# RP2350-MLX90393_4.net
KiCad netlist of a schematic drawn in EasyEDA Pro
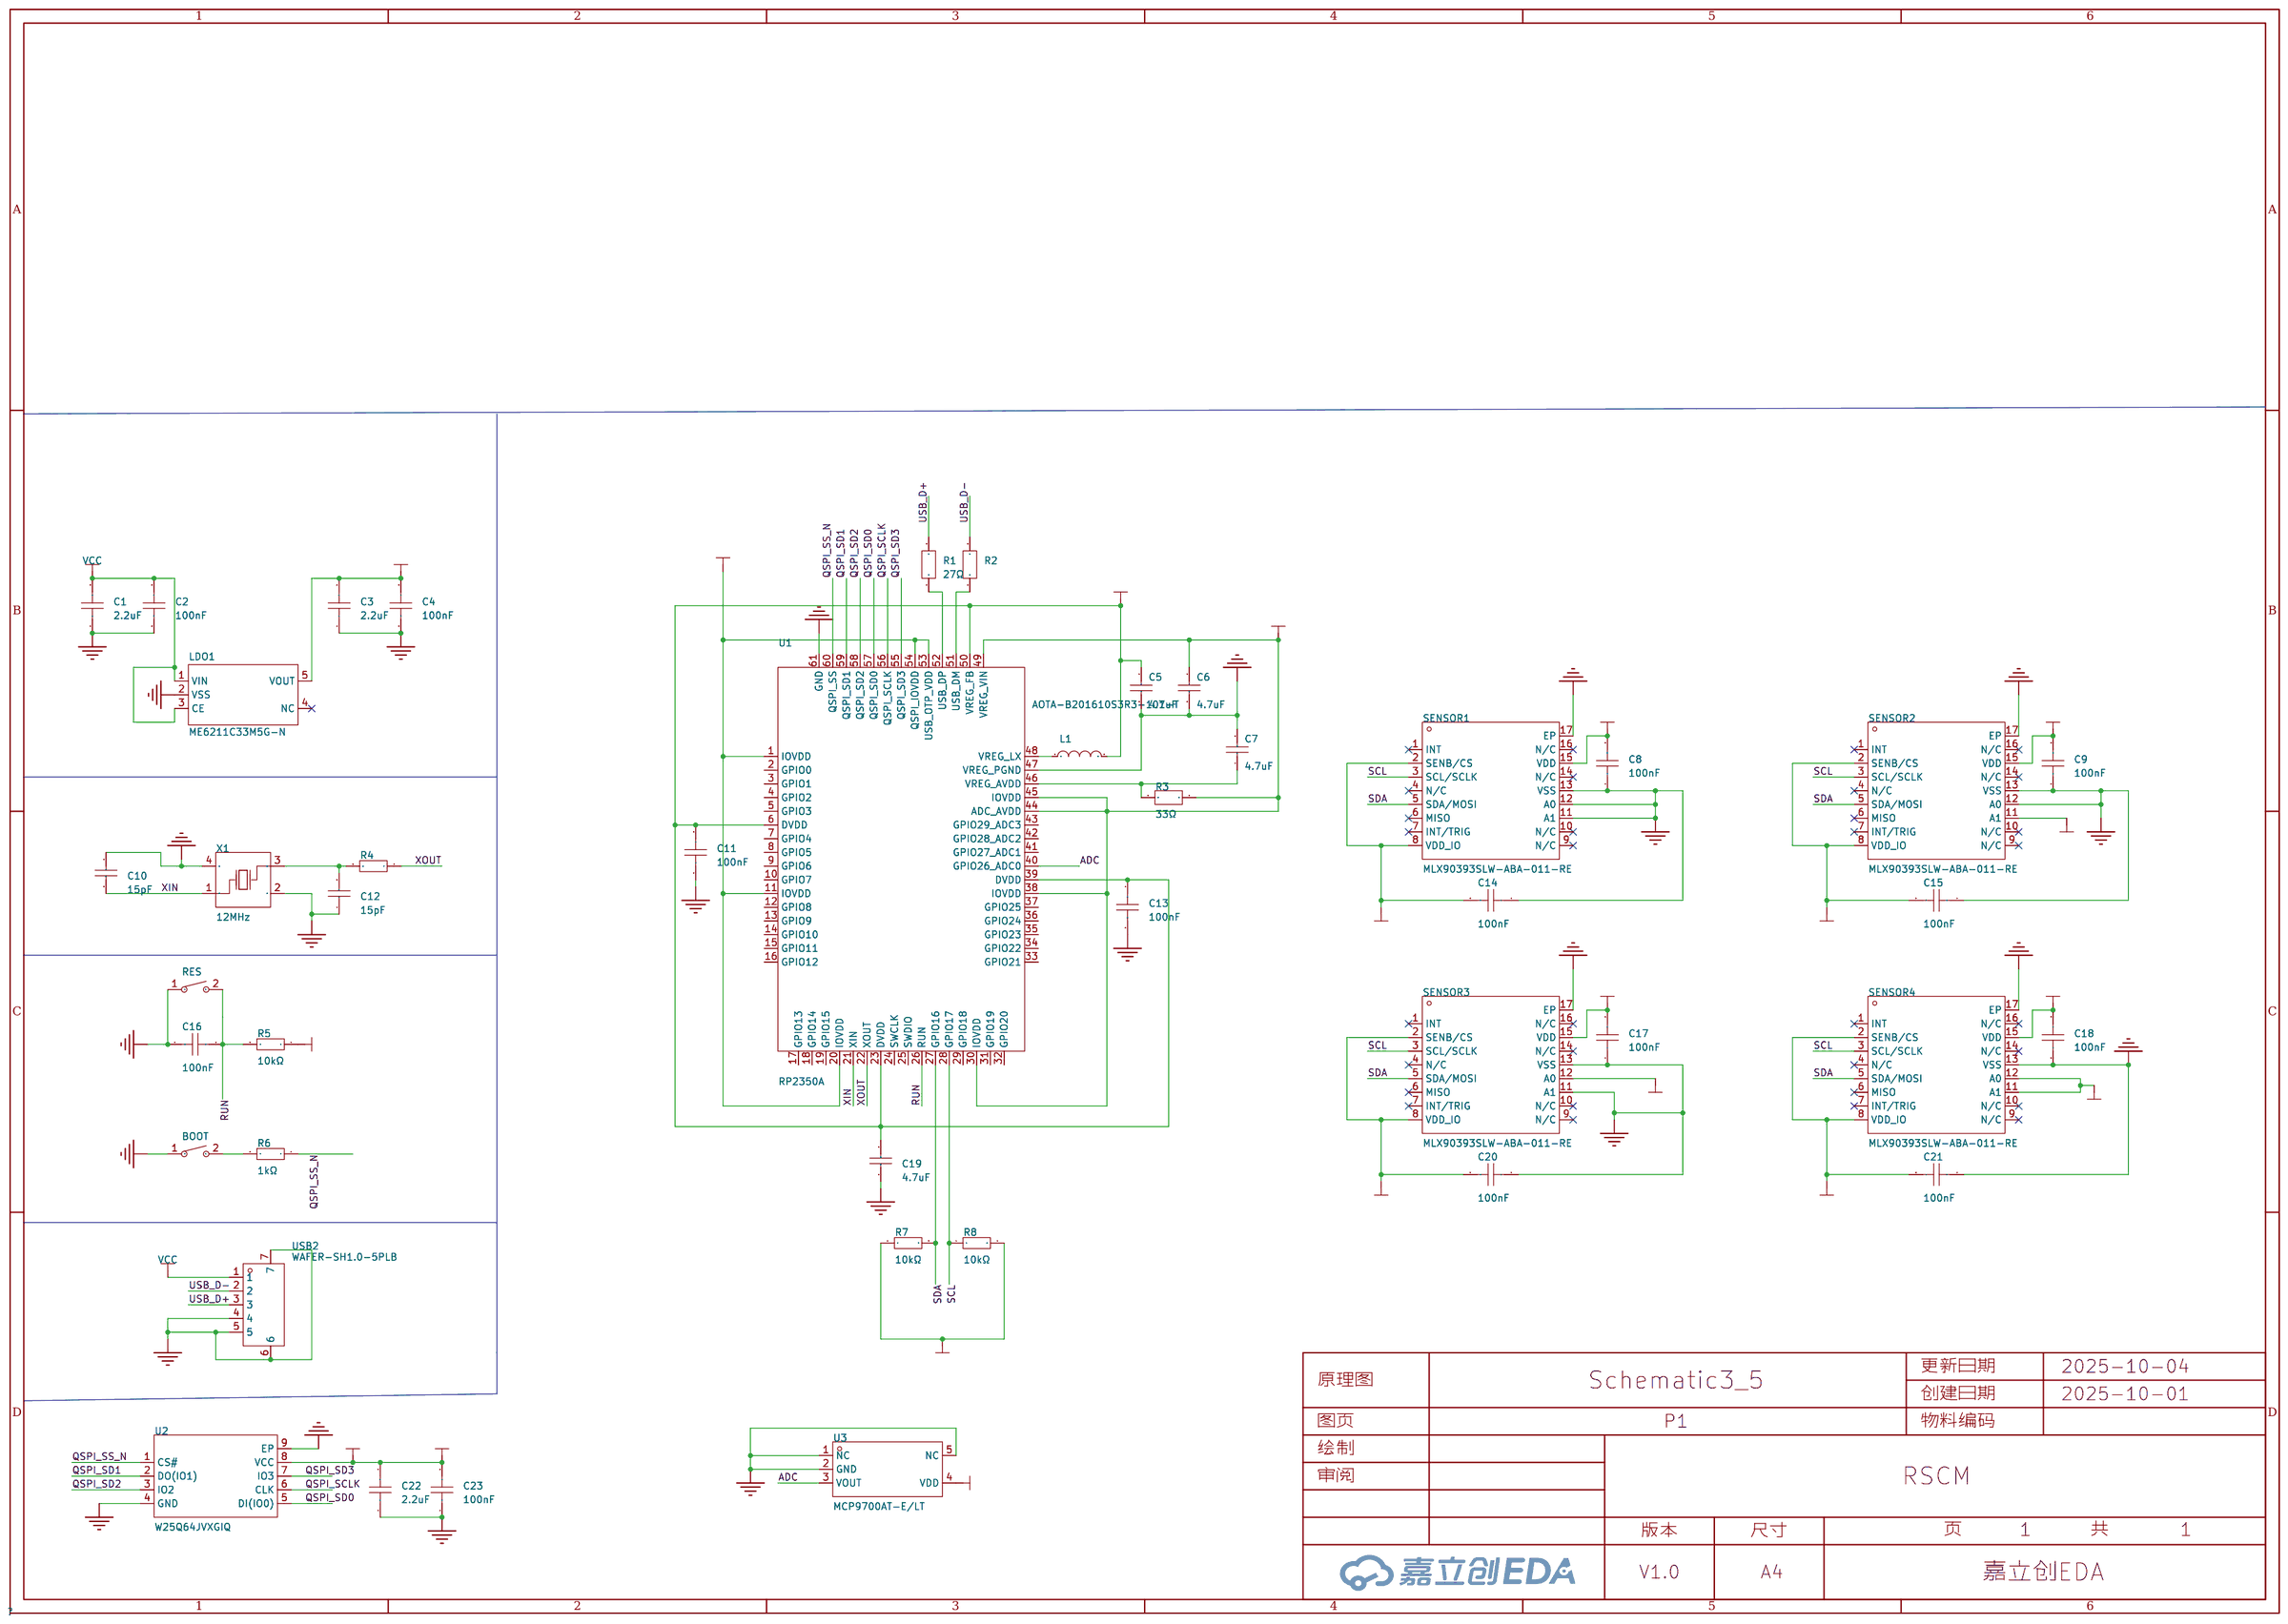
[diagram p0: schematic sheet]

(export (version "E")
  (design (tool "Eeschema 10.0.6"))
  (components
    (comp (ref "BOOT")
      (value "TS-1071AD-A1B3-D4")
      (footprint "easyedapro:SW-SMD_L4.0-W3.0-LS4.8")
      (description "电路结构:单刀单掷;安装方式:-;按钮形状:圆形按钮;带灯:-;作用力:250gf@±30gf;开关长度:4mm;开关宽度:3mm;开关高度:2mm;")
      (fields (field (name "Manufacturer") "Yuandi(元迪)"))
      (libsource (lib "easyedapro") (part "TS-1071AD-A1B3-D4"))
    )
    (comp (ref "C1")
      (value "2.2uF")
      (footprint "easyedapro:C0603")
      (description "容值:2.2uF;精度:±10%;额定电压:50V;材质(温度系数):X5R;")
      (fields
        (field (name "Manufacturer Part") "CL10A225KB8NNNC")
        (field (name "Manufacturer") "SAMSUNG(三星)")
      )
      (libsource (lib "easyedapro") (part "CL10A225KB8NNNC"))
    )
    (comp (ref "C2")
      (value "100nF")
      (footprint "easyedapro:C0603")
      (description "容值:100nF;精度:±10%;额定电压:50V;材质(温度系数):X7R;")
      (fields
        (field (name "Manufacturer Part") "CGA0603X7R104K500JT")
        (field (name "Manufacturer") "HRE(芯声)")
      )
      (libsource (lib "easyedapro") (part "CGA0603X7R104K500JT"))
    )
    (comp (ref "C3")
      (value "2.2uF")
      (footprint "easyedapro:C0603")
      (description "容值:2.2uF;精度:±10%;额定电压:50V;材质(温度系数):X5R;")
      (fields
        (field (name "Manufacturer Part") "CL10A225KB8NNNC")
        (field (name "Manufacturer") "SAMSUNG(三星)")
      )
      (libsource (lib "easyedapro") (part "CL10A225KB8NNNC"))
    )
    (comp (ref "C4")
      (value "100nF")
      (footprint "easyedapro:C0603")
      (description "容值:100nF;精度:±10%;额定电压:50V;材质(温度系数):X7R;")
      (fields
        (field (name "Manufacturer Part") "CGA0603X7R104K500JT")
        (field (name "Manufacturer") "HRE(芯声)")
      )
      (libsource (lib "easyedapro") (part "CGA0603X7R104K500JT"))
    )
    (comp (ref "C5")
      (value "4.7uF")
      (footprint "easyedapro:C0603")
      (description "温度系数:Y5V;精度:±20%;容值:4.7uF;额定电压:16V;")
      (fields (field (name "Manufacturer Part") "0603F475M160NT") (field (name "Manufacturer") "FH(风华)"))
      (libsource (lib "easyedapro") (part "0603F475M160NT"))
    )
    (comp (ref "C6")
      (value "4.7uF")
      (footprint "easyedapro:C0603")
      (description "温度系数:Y5V;精度:±20%;容值:4.7uF;额定电压:16V;")
      (fields (field (name "Manufacturer Part") "0603F475M160NT") (field (name "Manufacturer") "FH(风华)"))
      (libsource (lib "easyedapro") (part "0603F475M160NT"))
    )
    (comp (ref "C7")
      (value "4.7uF")
      (footprint "easyedapro:C0603")
      (description "温度系数:Y5V;精度:±20%;容值:4.7uF;额定电压:16V;")
      (fields (field (name "Manufacturer Part") "0603F475M160NT") (field (name "Manufacturer") "FH(风华)"))
      (libsource (lib "easyedapro") (part "0603F475M160NT"))
    )
    (comp (ref "C8")
      (value "100nF")
      (footprint "easyedapro:C0603")
      (description "容值:100nF;精度:±10%;额定电压:50V;材质(温度系数):X7R;")
      (fields
        (field (name "Manufacturer Part") "CGA0603X7R104K500JT")
        (field (name "Manufacturer") "HRE(芯声)")
      )
      (libsource (lib "easyedapro") (part "CGA0603X7R104K500JT"))
    )
    (comp (ref "C9")
      (value "100nF")
      (footprint "easyedapro:C0603")
      (description "容值:100nF;精度:±10%;额定电压:50V;材质(温度系数):X7R;")
      (fields
        (field (name "Manufacturer Part") "CGA0603X7R104K500JT")
        (field (name "Manufacturer") "HRE(芯声)")
      )
      (libsource (lib "easyedapro") (part "CGA0603X7R104K500JT"))
    )
    (comp (ref "C10")
      (value "15pF")
      (footprint "easyedapro:C0603")
      (description "容值:15pF;精度:±5%;额定电压:50V;材质(温度系数):NP0;")
      (fields
        (field (name "Manufacturer Part") "CC0603JRNPO9BN150")
        (field (name "Manufacturer") "YAGEO(国巨)")
      )
      (libsource (lib "easyedapro") (part "CC0603JRNPO9BN150"))
    )
    (comp (ref "C11")
      (value "100nF")
      (footprint "easyedapro:C0603")
      (description "容值:100nF;精度:±10%;额定电压:50V;材质(温度系数):X7R;")
      (fields
        (field (name "Manufacturer Part") "CGA0603X7R104K500JT")
        (field (name "Manufacturer") "HRE(芯声)")
      )
      (libsource (lib "easyedapro") (part "CGA0603X7R104K500JT"))
    )
    (comp (ref "C12")
      (value "15pF")
      (footprint "easyedapro:C0603")
      (description "容值:15pF;精度:±5%;额定电压:50V;材质(温度系数):NP0;")
      (fields
        (field (name "Manufacturer Part") "CC0603JRNPO9BN150")
        (field (name "Manufacturer") "YAGEO(国巨)")
      )
      (libsource (lib "easyedapro") (part "CC0603JRNPO9BN150"))
    )
    (comp (ref "C13")
      (value "100nF")
      (footprint "easyedapro:C0603")
      (description "容值:100nF;精度:±10%;额定电压:50V;材质(温度系数):X7R;")
      (fields
        (field (name "Manufacturer Part") "CGA0603X7R104K500JT")
        (field (name "Manufacturer") "HRE(芯声)")
      )
      (libsource (lib "easyedapro") (part "CGA0603X7R104K500JT"))
    )
    (comp (ref "C14")
      (value "100nF")
      (footprint "easyedapro:C0603")
      (description "容值:100nF;精度:±10%;额定电压:50V;材质(温度系数):X7R;")
      (fields
        (field (name "Manufacturer Part") "CGA0603X7R104K500JT")
        (field (name "Manufacturer") "HRE(芯声)")
      )
      (libsource (lib "easyedapro") (part "CGA0603X7R104K500JT"))
    )
    (comp (ref "C15")
      (value "100nF")
      (footprint "easyedapro:C0603")
      (description "容值:100nF;精度:±10%;额定电压:50V;材质(温度系数):X7R;")
      (fields
        (field (name "Manufacturer Part") "CGA0603X7R104K500JT")
        (field (name "Manufacturer") "HRE(芯声)")
      )
      (libsource (lib "easyedapro") (part "CGA0603X7R104K500JT"))
    )
    (comp (ref "C16")
      (value "100nF")
      (footprint "easyedapro:C0603")
      (description "容值:100nF;精度:±10%;额定电压:50V;材质(温度系数):X7R;")
      (fields
        (field (name "Manufacturer Part") "CGA0603X7R104K500JT")
        (field (name "Manufacturer") "HRE(芯声)")
      )
      (libsource (lib "easyedapro") (part "CGA0603X7R104K500JT"))
    )
    (comp (ref "C17")
      (value "100nF")
      (footprint "easyedapro:C0603")
      (description "容值:100nF;精度:±10%;额定电压:50V;材质(温度系数):X7R;")
      (fields
        (field (name "Manufacturer Part") "CGA0603X7R104K500JT")
        (field (name "Manufacturer") "HRE(芯声)")
      )
      (libsource (lib "easyedapro") (part "CGA0603X7R104K500JT"))
    )
    (comp (ref "C18")
      (value "100nF")
      (footprint "easyedapro:C0603")
      (description "容值:100nF;精度:±10%;额定电压:50V;材质(温度系数):X7R;")
      (fields
        (field (name "Manufacturer Part") "CGA0603X7R104K500JT")
        (field (name "Manufacturer") "HRE(芯声)")
      )
      (libsource (lib "easyedapro") (part "CGA0603X7R104K500JT"))
    )
    (comp (ref "C19")
      (value "4.7uF")
      (footprint "easyedapro:C0603")
      (description "温度系数:Y5V;精度:±20%;容值:4.7uF;额定电压:16V;")
      (fields (field (name "Manufacturer Part") "0603F475M160NT") (field (name "Manufacturer") "FH(风华)"))
      (libsource (lib "easyedapro") (part "0603F475M160NT"))
    )
    (comp (ref "C20")
      (value "100nF")
      (footprint "easyedapro:C0603")
      (description "容值:100nF;精度:±10%;额定电压:50V;材质(温度系数):X7R;")
      (fields
        (field (name "Manufacturer Part") "CGA0603X7R104K500JT")
        (field (name "Manufacturer") "HRE(芯声)")
      )
      (libsource (lib "easyedapro") (part "CGA0603X7R104K500JT"))
    )
    (comp (ref "C21")
      (value "100nF")
      (footprint "easyedapro:C0603")
      (description "容值:100nF;精度:±10%;额定电压:50V;材质(温度系数):X7R;")
      (fields
        (field (name "Manufacturer Part") "CGA0603X7R104K500JT")
        (field (name "Manufacturer") "HRE(芯声)")
      )
      (libsource (lib "easyedapro") (part "CGA0603X7R104K500JT"))
    )
    (comp (ref "C22")
      (value "2.2uF")
      (footprint "easyedapro:C0603")
      (description "容值:2.2uF;精度:±10%;额定电压:50V;材质(温度系数):X5R;")
      (fields
        (field (name "Manufacturer Part") "CL10A225KB8NNNC")
        (field (name "Manufacturer") "SAMSUNG(三星)")
      )
      (libsource (lib "easyedapro") (part "CL10A225KB8NNNC"))
    )
    (comp (ref "C23")
      (value "100nF")
      (footprint "easyedapro:C0603")
      (description "容值:100nF;精度:±10%;额定电压:50V;材质(温度系数):X7R;")
      (fields
        (field (name "Manufacturer Part") "CGA0603X7R104K500JT")
        (field (name "Manufacturer") "HRE(芯声)")
      )
      (libsource (lib "easyedapro") (part "CGA0603X7R104K500JT"))
    )
    (comp (ref "L1")
      (value "AOTA-B201610S3R3-101-T")
      (footprint "easyedapro:IND-SMD_L2.0-W1.6_AOTA-B201610S3R3-101-T")
      (fields (field (name "Manufacturer") "ABRACON"))
      (libsource (lib "easyedapro") (part "AOTA-B201610S3R3-101-T"))
    )
    (comp (ref "LDO1")
      (value "ME6211C33M5G-N")
      (footprint "easyedapro:SOT-23-5_L3.0-W1.7-P0.95-LS2.8-BL")
      (description "输出类型:固定;工作电压:6V;输出电压:3.3V;输出电流:500mA;电源纹波抑制比(PSRR):70dB@(1kHz)；62dB@(10kHz);输出极性:正极;")
      (fields (field (name "Manufacturer") "MICRONE(南京微盟)"))
      (libsource (lib "easyedapro") (part "ME6211C33M5G-N"))
    )
    (comp (ref "R1")
      (value "27Ω")
      (footprint "easyedapro:R0603")
      (description "电阻类型:厚膜电阻;阻值:27Ω;精度:±1%;功率:100mW;工作电压:75V;温度系数:±100ppm/°C;")
      (fields (field (name "Manufacturer Part") "FRC0603F27R0TS") (field (name "Manufacturer") "FOJAN(富捷)"))
      (libsource (lib "easyedapro") (part "FRC0603F27R0TS"))
    )
    (comp (ref "R2")
      (value "27Ω")
      (footprint "easyedapro:R0603")
      (description "电阻类型:厚膜电阻;阻值:27Ω;精度:±1%;功率:100mW;工作电压:75V;温度系数:±100ppm/°C;")
      (fields (field (name "Manufacturer Part") "FRC0603F27R0TS") (field (name "Manufacturer") "FOJAN(富捷)"))
      (libsource (lib "easyedapro") (part "FRC0603F27R0TS"))
    )
    (comp (ref "R3")
      (value "33Ω")
      (footprint "easyedapro:R0603")
      (description "电阻类型:厚膜电阻;阻值:33Ω;精度:±1%;功率:100mW;工作电压:75V;温度系数:±100ppm/°C;")
      (fields (field (name "Manufacturer Part") "FRC0603F33R0TS") (field (name "Manufacturer") "FOJAN(富捷)"))
      (libsource (lib "easyedapro") (part "FRC0603F33R0TS"))
    )
    (comp (ref "R4")
      (value "1kΩ")
      (footprint "easyedapro:R0603")
      (description "电阻类型:厚膜电阻;阻值:1kΩ;精度:±1%;功率:100mW;最大工作电压:75V;温度系数:±100ppm/°C;")
      (fields
        (field (name "Manufacturer Part") "0603WAF1001T5E")
        (field (name "Manufacturer") "UNI-ROYAL(厚声)")
      )
      (libsource (lib "easyedapro") (part "0603WAF1001T5E"))
    )
    (comp (ref "R5")
      (value "10kΩ")
      (footprint "easyedapro:R0603")
      (description "电阻类型:厚膜电阻;阻值:10kΩ;精度:±1%;功率:100mW;")
      (fields (field (name "Manufacturer Part") "RC0603FR-0710KL") (field (name "Manufacturer") "YAGEO(国巨)"))
      (libsource (lib "easyedapro") (part "RC0603FR-0710KL"))
    )
    (comp (ref "R6")
      (value "1kΩ")
      (footprint "easyedapro:R0603")
      (description "电阻类型:厚膜电阻;阻值:10kΩ;精度:±1%;功率:100mW;")
      (fields (field (name "Manufacturer Part") "RC0603FR-0710KL") (field (name "Manufacturer") "YAGEO(国巨)"))
      (libsource (lib "easyedapro") (part "RC0603FR-0710KL"))
    )
    (comp (ref "R7")
      (value "10kΩ")
      (footprint "easyedapro:R0603")
      (description "电阻类型:厚膜电阻;阻值:4.7kΩ;精度:±1%;功率:100mW;最大工作电压:75V;温度系数:±100ppm/°C;")
      (fields
        (field (name "Manufacturer Part") "0603WAF4701T5E")
        (field (name "Manufacturer") "UNI-ROYAL(厚声)")
      )
      (libsource (lib "easyedapro") (part "0603WAF4701T5E"))
    )
    (comp (ref "R8")
      (value "10kΩ")
      (footprint "easyedapro:R0603")
      (description "电阻类型:厚膜电阻;阻值:4.7kΩ;精度:±1%;功率:100mW;最大工作电压:75V;温度系数:±100ppm/°C;")
      (fields
        (field (name "Manufacturer Part") "0603WAF4701T5E")
        (field (name "Manufacturer") "UNI-ROYAL(厚声)")
      )
      (libsource (lib "easyedapro") (part "0603WAF4701T5E"))
    )
    (comp (ref "RES")
      (value "TS-1071AD-A1B3-D4")
      (footprint "easyedapro:SW-SMD_L4.0-W3.0-LS4.8")
      (description "电路结构:单刀单掷;安装方式:-;按钮形状:圆形按钮;带灯:-;作用力:250gf@±30gf;开关长度:4mm;开关宽度:3mm;开关高度:2mm;")
      (fields (field (name "Manufacturer") "Yuandi(元迪)"))
      (libsource (lib "easyedapro") (part "TS-1071AD-A1B3-D4"))
    )
    (comp (ref "SENSOR1")
      (value "MLX90393SLW-ABA-011-RE")
      (footprint "easyedapro:VQFN-16_L3.0-W3.0-P0.50-BL-EP1.7")
      (description "三轴磁传感器")
      (fields (field (name "Manufacturer") "Melexis(比利时迈来芯)"))
      (libsource (lib "easyedapro") (part "MLX90393SLW-ABA-011-RE"))
    )
    (comp (ref "SENSOR2")
      (value "MLX90393SLW-ABA-011-RE")
      (footprint "easyedapro:VQFN-16_L3.0-W3.0-P0.50-BL-EP1.7")
      (description "三轴磁传感器")
      (fields (field (name "Manufacturer") "Melexis(比利时迈来芯)"))
      (libsource (lib "easyedapro") (part "MLX90393SLW-ABA-011-RE"))
    )
    (comp (ref "SENSOR3")
      (value "MLX90393SLW-ABA-011-RE")
      (footprint "easyedapro:VQFN-16_L3.0-W3.0-P0.50-BL-EP1.7")
      (description "三轴磁传感器")
      (fields (field (name "Manufacturer") "Melexis(比利时迈来芯)"))
      (libsource (lib "easyedapro") (part "MLX90393SLW-ABA-011-RE"))
    )
    (comp (ref "SENSOR4")
      (value "MLX90393SLW-ABA-011-RE")
      (footprint "easyedapro:VQFN-16_L3.0-W3.0-P0.50-BL-EP1.7")
      (description "三轴磁传感器")
      (fields (field (name "Manufacturer") "Melexis(比利时迈来芯)"))
      (libsource (lib "easyedapro") (part "MLX90393SLW-ABA-011-RE"))
    )
    (comp (ref "U1")
      (value "RP2350A")
      (footprint "easyedapro:QFN-60_L7.0-W7.0-P0.40-TL-EP3.4")
      (description "推荐配套ABRACON  C42411119使用")
      (fields (field (name "Manufacturer") "Raspberry Pi(树莓派)"))
      (libsource (lib "easyedapro") (part "RP2350A_C42411118"))
    )
    (comp (ref "U2")
      (value "W25Q64JVXGIQ")
      (footprint "easyedapro:XSON-8_L4.0-W4.0-P0.80-TL-EP")
      (fields (field (name "Manufacturer") "WINBOND(华邦)"))
      (libsource (lib "easyedapro") (part "W25Q64JVXGIQ"))
    )
    (comp (ref "U3")
      (value "MCP9700AT-E/LT")
      (footprint "easyedapro:SC-70-5_L2.1-W1.3-P0.65-LS2.1-TL")
      (fields (field (name "Manufacturer") "MICROCHIP(美国微芯)"))
      (libsource (lib "easyedapro") (part "MCP9700AT-E/LT_C97546"))
    )
    (comp (ref "USB2")
      (value "WAFER-SH1.0-5PLB")
      (footprint "easyedapro:CONN-SMD-5P-P1.00_BM05B-SRSS-TB-LF-SN")
      (fields (field (name "Manufacturer") "XUNPU(讯普)"))
      (libsource (lib "easyedapro") (part "WAFER-SH1.0-5PLB"))
    )
    (comp (ref "X1")
      (value "12MHz")
      (footprint "easyedapro:OSC-SMD_4P-L3.2-W2.5-BL")
      (description "晶振类型:贴片晶振;频率:12MHz;常温频差:±10ppm;外接负载电容:20pF;频率稳定度(全温):±20ppm;")
      (fields (field (name "Manufacturer Part") "X322512MSB4SI") (field (name "Manufacturer") "YXC(扬兴晶振)"))
      (libsource (lib "easyedapro") (part "X322512MSB4SI"))
    )
  )
  (nets
    (net (code "1") (name "+1V1") (class "Default")
      (node (ref "C11") (pin "2") (pinfunction "2_2") (pintype "unspecified"))
      (node (ref "C13") (pin "1") (pinfunction "1_1") (pintype "unspecified"))
      (node (ref "C19") (pin "2") (pinfunction "2_2") (pintype "input"))
      (node (ref "C5") (pin "1") (pinfunction "1_1") (pintype "input"))
      (node (ref "L1") (pin "2") (pinfunction "2_2") (pintype "unspecified"))
      (node (ref "U1") (pin "23") (pinfunction "DVDD_23") (pintype "unspecified"))
      (node (ref "U1") (pin "39") (pinfunction "DVDD_39") (pintype "unspecified"))
      (node (ref "U1") (pin "50") (pinfunction "VREG_FB_50") (pintype "unspecified"))
      (node (ref "U1") (pin "6") (pinfunction "DVDD_6") (pintype "unspecified"))
    )
    (net (code "2") (name "+3V3") (class "Default")
      (node (ref "C14") (pin "2") (pinfunction "2_2") (pintype "unspecified"))
      (node (ref "C15") (pin "2") (pinfunction "2_2") (pintype "unspecified"))
      (node (ref "C17") (pin "2") (pinfunction "2_2") (pintype "unspecified"))
      (node (ref "C18") (pin "2") (pinfunction "2_2") (pintype "unspecified"))
      (node (ref "C20") (pin "2") (pinfunction "2_2") (pintype "unspecified"))
      (node (ref "C21") (pin "2") (pinfunction "2_2") (pintype "unspecified"))
      (node (ref "C22") (pin "2") (pinfunction "2_2") (pintype "unspecified"))
      (node (ref "C23") (pin "2") (pinfunction "2_2") (pintype "unspecified"))
      (node (ref "C3") (pin "2") (pinfunction "2_2") (pintype "unspecified"))
      (node (ref "C4") (pin "2") (pinfunction "2_2") (pintype "unspecified"))
      (node (ref "C6") (pin "1") (pinfunction "1_1") (pintype "input"))
      (node (ref "C8") (pin "2") (pinfunction "2_2") (pintype "unspecified"))
      (node (ref "C9") (pin "2") (pinfunction "2_2") (pintype "unspecified"))
      (node (ref "LDO1") (pin "5") (pinfunction "VOUT_5") (pintype "unspecified"))
      (node (ref "R3") (pin "1") (pinfunction "1_1") (pintype "unspecified"))
      (node (ref "R5") (pin "1") (pinfunction "1_1") (pintype "input"))
      (node (ref "R7") (pin "1") (pinfunction "1_1") (pintype "input"))
      (node (ref "R8") (pin "2") (pinfunction "2_2") (pintype "input"))
      (node (ref "SENSOR1") (pin "15") (pinfunction "VDD_15") (pintype "unspecified"))
      (node (ref "SENSOR1") (pin "2") (pinfunction "SENB/CS_2") (pintype "unspecified"))
      (node (ref "SENSOR1") (pin "8") (pinfunction "VDD_IO_8") (pintype "unspecified"))
      (node (ref "SENSOR2") (pin "11") (pinfunction "A1_11") (pintype "unspecified"))
      (node (ref "SENSOR2") (pin "15") (pinfunction "VDD_15") (pintype "unspecified"))
      (node (ref "SENSOR2") (pin "2") (pinfunction "SENB/CS_2") (pintype "unspecified"))
      (node (ref "SENSOR2") (pin "8") (pinfunction "VDD_IO_8") (pintype "unspecified"))
      (node (ref "SENSOR3") (pin "12") (pinfunction "A0_12") (pintype "unspecified"))
      (node (ref "SENSOR3") (pin "15") (pinfunction "VDD_15") (pintype "unspecified"))
      (node (ref "SENSOR3") (pin "2") (pinfunction "SENB/CS_2") (pintype "unspecified"))
      (node (ref "SENSOR3") (pin "8") (pinfunction "VDD_IO_8") (pintype "unspecified"))
      (node (ref "SENSOR4") (pin "11") (pinfunction "A1_11") (pintype "unspecified"))
      (node (ref "SENSOR4") (pin "12") (pinfunction "A0_12") (pintype "unspecified"))
      (node (ref "SENSOR4") (pin "15") (pinfunction "VDD_15") (pintype "unspecified"))
      (node (ref "SENSOR4") (pin "2") (pinfunction "SENB/CS_2") (pintype "unspecified"))
      (node (ref "SENSOR4") (pin "8") (pinfunction "VDD_IO_8") (pintype "unspecified"))
      (node (ref "U1") (pin "1") (pinfunction "IOVDD_1") (pintype "unspecified"))
      (node (ref "U1") (pin "11") (pinfunction "IOVDD_11") (pintype "unspecified"))
      (node (ref "U1") (pin "20") (pinfunction "IOVDD_20") (pintype "unspecified"))
      (node (ref "U1") (pin "30") (pinfunction "IOVDD_30") (pintype "unspecified"))
      (node (ref "U1") (pin "38") (pinfunction "IOVDD_38") (pintype "unspecified"))
      (node (ref "U1") (pin "44") (pinfunction "ADC_AVDD_44") (pintype "unspecified"))
      (node (ref "U1") (pin "45") (pinfunction "IOVDD_45") (pintype "unspecified"))
      (node (ref "U1") (pin "49") (pinfunction "VREG_VIN_49") (pintype "unspecified"))
      (node (ref "U1") (pin "53") (pinfunction "USB_OTP_VDD_53") (pintype "unspecified"))
      (node (ref "U1") (pin "54") (pinfunction "QSPI_IOVDD_54") (pintype "unspecified"))
      (node (ref "U2") (pin "8") (pinfunction "VCC_8") (pintype "unspecified"))
      (node (ref "U3") (pin "4") (pinfunction "VDD_4") (pintype "unspecified"))
    )
    (net (code "3") (name "/ADC") (class "Default")
      (node (ref "U1") (pin "40") (pinfunction "GPIO26_ADC0_40") (pintype "unspecified"))
      (node (ref "U3") (pin "3") (pinfunction "VOUT_3") (pintype "unspecified"))
    )
    (net (code "4") (name "/QSPI_SCLK") (class "Default")
      (node (ref "U1") (pin "56") (pinfunction "QSPI_SCLK_56") (pintype "unspecified"))
      (node (ref "U2") (pin "6") (pinfunction "CLK_6") (pintype "unspecified"))
    )
    (net (code "5") (name "/QSPI_SD0") (class "Default")
      (node (ref "U1") (pin "57") (pinfunction "QSPI_SD0_57") (pintype "unspecified"))
      (node (ref "U2") (pin "5") (pinfunction "DI(IO0)_5") (pintype "unspecified"))
    )
    (net (code "6") (name "/QSPI_SD1") (class "Default")
      (node (ref "U1") (pin "59") (pinfunction "QSPI_SD1_59") (pintype "unspecified"))
      (node (ref "U2") (pin "2") (pinfunction "DO(IO1)_2") (pintype "unspecified"))
    )
    (net (code "7") (name "/QSPI_SD2") (class "Default")
      (node (ref "U1") (pin "58") (pinfunction "QSPI_SD2_58") (pintype "unspecified"))
      (node (ref "U2") (pin "3") (pinfunction "IO2_3") (pintype "unspecified"))
    )
    (net (code "8") (name "/QSPI_SD3") (class "Default")
      (node (ref "U1") (pin "55") (pinfunction "QSPI_SD3_55") (pintype "unspecified"))
      (node (ref "U2") (pin "7") (pinfunction "IO3_7") (pintype "unspecified"))
    )
    (net (code "9") (name "/QSPI_SS_N") (class "Default")
      (node (ref "R6") (pin "1") (pinfunction "1_1") (pintype "input"))
      (node (ref "U1") (pin "60") (pinfunction "QSPI_SS_60") (pintype "unspecified"))
      (node (ref "U2") (pin "1") (pinfunction "CS#_1") (pintype "unspecified"))
    )
    (net (code "10") (name "/RUN") (class "Default")
      (node (ref "C16") (pin "2") (pinfunction "2_2") (pintype "unspecified"))
      (node (ref "R5") (pin "2") (pinfunction "2_2") (pintype "input"))
      (node (ref "RES") (pin "2") (pinfunction "2_2") (pintype "input"))
      (node (ref "U1") (pin "26") (pinfunction "RUN_26") (pintype "unspecified"))
    )
    (net (code "11") (name "/SCL") (class "Default")
      (node (ref "R8") (pin "1") (pinfunction "1_1") (pintype "input"))
      (node (ref "SENSOR1") (pin "3") (pinfunction "SCL/SCLK_3") (pintype "unspecified"))
      (node (ref "SENSOR2") (pin "3") (pinfunction "SCL/SCLK_3") (pintype "unspecified"))
      (node (ref "SENSOR3") (pin "3") (pinfunction "SCL/SCLK_3") (pintype "unspecified"))
      (node (ref "SENSOR4") (pin "3") (pinfunction "SCL/SCLK_3") (pintype "unspecified"))
      (node (ref "U1") (pin "28") (pinfunction "GPIO17_28") (pintype "unspecified"))
    )
    (net (code "12") (name "/SDA") (class "Default")
      (node (ref "R7") (pin "2") (pinfunction "2_2") (pintype "input"))
      (node (ref "SENSOR1") (pin "5") (pinfunction "SDA/MOSI_5") (pintype "unspecified"))
      (node (ref "SENSOR2") (pin "5") (pinfunction "SDA/MOSI_5") (pintype "unspecified"))
      (node (ref "SENSOR3") (pin "5") (pinfunction "SDA/MOSI_5") (pintype "unspecified"))
      (node (ref "SENSOR4") (pin "5") (pinfunction "SDA/MOSI_5") (pintype "unspecified"))
      (node (ref "U1") (pin "27") (pinfunction "GPIO16_27") (pintype "unspecified"))
    )
    (net (code "13") (name "/USB_D+") (class "Default")
      (node (ref "R1") (pin "2") (pinfunction "2_2") (pintype "unspecified"))
      (node (ref "USB2") (pin "3") (pinfunction "3_3") (pintype "unspecified"))
    )
    (net (code "14") (name "/USB_D-") (class "Default")
      (node (ref "R2") (pin "2") (pinfunction "2_2") (pintype "unspecified"))
      (node (ref "USB2") (pin "2") (pinfunction "2_2") (pintype "unspecified"))
    )
    (net (code "15") (name "/XIN") (class "Default")
      (node (ref "C10") (pin "1") (pinfunction "1_1") (pintype "input"))
      (node (ref "U1") (pin "21") (pinfunction "XIN_21") (pintype "unspecified"))
      (node (ref "X1") (pin "1") (pinfunction "OSC1_1") (pintype "unspecified"))
    )
    (net (code "16") (name "/XOUT") (class "Default")
      (node (ref "R4") (pin "1") (pinfunction "1_1") (pintype "input"))
      (node (ref "U1") (pin "22") (pinfunction "XOUT_22") (pintype "unspecified"))
    )
    (net (code "17") (name "GND") (class "Default")
      (node (ref "BOOT") (pin "1") (pinfunction "1_1") (pintype "input"))
      (node (ref "C1") (pin "1") (pinfunction "1_1") (pintype "unspecified"))
      (node (ref "C10") (pin "2") (pinfunction "2_2") (pintype "input"))
      (node (ref "C11") (pin "1") (pinfunction "1_1") (pintype "unspecified"))
      (node (ref "C12") (pin "1") (pinfunction "1_1") (pintype "input"))
      (node (ref "C13") (pin "2") (pinfunction "2_2") (pintype "unspecified"))
      (node (ref "C14") (pin "1") (pinfunction "1_1") (pintype "unspecified"))
      (node (ref "C15") (pin "1") (pinfunction "1_1") (pintype "unspecified"))
      (node (ref "C16") (pin "1") (pinfunction "1_1") (pintype "unspecified"))
      (node (ref "C17") (pin "1") (pinfunction "1_1") (pintype "unspecified"))
      (node (ref "C18") (pin "1") (pinfunction "1_1") (pintype "unspecified"))
      (node (ref "C19") (pin "1") (pinfunction "1_1") (pintype "input"))
      (node (ref "C2") (pin "1") (pinfunction "1_1") (pintype "unspecified"))
      (node (ref "C20") (pin "1") (pinfunction "1_1") (pintype "unspecified"))
      (node (ref "C21") (pin "1") (pinfunction "1_1") (pintype "unspecified"))
      (node (ref "C22") (pin "1") (pinfunction "1_1") (pintype "unspecified"))
      (node (ref "C23") (pin "1") (pinfunction "1_1") (pintype "unspecified"))
      (node (ref "C3") (pin "1") (pinfunction "1_1") (pintype "unspecified"))
      (node (ref "C4") (pin "1") (pinfunction "1_1") (pintype "unspecified"))
      (node (ref "C5") (pin "2") (pinfunction "2_2") (pintype "input"))
      (node (ref "C6") (pin "2") (pinfunction "2_2") (pintype "input"))
      (node (ref "C7") (pin "2") (pinfunction "2_2") (pintype "input"))
      (node (ref "C8") (pin "1") (pinfunction "1_1") (pintype "unspecified"))
      (node (ref "C9") (pin "1") (pinfunction "1_1") (pintype "unspecified"))
      (node (ref "LDO1") (pin "2") (pinfunction "VSS_2") (pintype "unspecified"))
      (node (ref "RES") (pin "1") (pinfunction "1_1") (pintype "input"))
      (node (ref "SENSOR1") (pin "11") (pinfunction "A1_11") (pintype "unspecified"))
      (node (ref "SENSOR1") (pin "12") (pinfunction "A0_12") (pintype "unspecified"))
      (node (ref "SENSOR1") (pin "13") (pinfunction "VSS_13") (pintype "unspecified"))
      (node (ref "SENSOR1") (pin "17") (pinfunction "EP_17") (pintype "unspecified"))
      (node (ref "SENSOR2") (pin "12") (pinfunction "A0_12") (pintype "unspecified"))
      (node (ref "SENSOR2") (pin "13") (pinfunction "VSS_13") (pintype "unspecified"))
      (node (ref "SENSOR2") (pin "17") (pinfunction "EP_17") (pintype "unspecified"))
      (node (ref "SENSOR3") (pin "11") (pinfunction "A1_11") (pintype "unspecified"))
      (node (ref "SENSOR3") (pin "13") (pinfunction "VSS_13") (pintype "unspecified"))
      (node (ref "SENSOR3") (pin "17") (pinfunction "EP_17") (pintype "unspecified"))
      (node (ref "SENSOR4") (pin "13") (pinfunction "VSS_13") (pintype "unspecified"))
      (node (ref "SENSOR4") (pin "17") (pinfunction "EP_17") (pintype "unspecified"))
      (node (ref "U1") (pin "47") (pinfunction "VREG_PGND_47") (pintype "unspecified"))
      (node (ref "U1") (pin "61") (pinfunction "GND_61") (pintype "unspecified"))
      (node (ref "U2") (pin "4") (pinfunction "GND_4") (pintype "unspecified"))
      (node (ref "U2") (pin "9") (pinfunction "EP_9") (pintype "unspecified"))
      (node (ref "U3") (pin "1") (pinfunction "NC_1") (pintype "unspecified"))
      (node (ref "U3") (pin "2") (pinfunction "GND_2") (pintype "unspecified"))
      (node (ref "U3") (pin "5") (pinfunction "NC_5") (pintype "unspecified"))
      (node (ref "USB2") (pin "4") (pinfunction "4_4") (pintype "unspecified"))
      (node (ref "USB2") (pin "5") (pinfunction "5_5") (pintype "unspecified"))
      (node (ref "USB2") (pin "6") (pinfunction "6_6") (pintype "unspecified"))
      (node (ref "USB2") (pin "7") (pinfunction "7_7") (pintype "unspecified"))
      (node (ref "X1") (pin "2") (pinfunction "GND_2") (pintype "unspecified"))
      (node (ref "X1") (pin "4") (pinfunction "GND_4") (pintype "unspecified"))
    )
    (net (code "18") (name "Net-(BOOT-Pad2)") (class "Default")
      (node (ref "BOOT") (pin "2") (pinfunction "2_2") (pintype "input"))
      (node (ref "R6") (pin "2") (pinfunction "2_2") (pintype "input"))
    )
    (net (code "19") (name "Net-(U1-USB_DM)") (class "Default")
      (node (ref "R2") (pin "1") (pinfunction "1_1") (pintype "unspecified"))
      (node (ref "U1") (pin "51") (pinfunction "USB_DM_51") (pintype "unspecified"))
    )
    (net (code "20") (name "Net-(U1-USB_DP)") (class "Default")
      (node (ref "R1") (pin "1") (pinfunction "1_1") (pintype "unspecified"))
      (node (ref "U1") (pin "52") (pinfunction "USB_DP_52") (pintype "unspecified"))
    )
    (net (code "21") (name "Net-(U1-VREG_AVDD)") (class "Default")
      (node (ref "C7") (pin "1") (pinfunction "1_1") (pintype "input"))
      (node (ref "R3") (pin "2") (pinfunction "2_2") (pintype "unspecified"))
      (node (ref "U1") (pin "46") (pinfunction "VREG_AVDD_46") (pintype "unspecified"))
    )
    (net (code "22") (name "Net-(U1-VREG_LX)") (class "Default")
      (node (ref "L1") (pin "1") (pinfunction "1_1") (pintype "unspecified"))
      (node (ref "U1") (pin "48") (pinfunction "VREG_LX_48") (pintype "unspecified"))
    )
    (net (code "23") (name "Net-(X1-OSC2)") (class "Default")
      (node (ref "C12") (pin "2") (pinfunction "2_2") (pintype "input"))
      (node (ref "R4") (pin "2") (pinfunction "2_2") (pintype "input"))
      (node (ref "X1") (pin "3") (pinfunction "OSC2_3") (pintype "unspecified"))
    )
    (net (code "24") (name "VCC") (class "Default")
      (node (ref "C1") (pin "2") (pinfunction "2_2") (pintype "unspecified"))
      (node (ref "C2") (pin "2") (pinfunction "2_2") (pintype "unspecified"))
      (node (ref "LDO1") (pin "1") (pinfunction "VIN_1") (pintype "unspecified"))
      (node (ref "LDO1") (pin "3") (pinfunction "CE_3") (pintype "unspecified"))
      (node (ref "USB2") (pin "1") (pinfunction "1_1") (pintype "unspecified"))
    )
    (net (code "25") (name "unconnected-(LDO1-NC-Pad4)") (class "Default")
      (node (ref "LDO1") (pin "4") (pinfunction "NC_4") (pintype "unspecified+no_connect"))
    )
    (net (code "26") (name "unconnected-(SENSOR1-INT-Pad1)") (class "Default")
      (node (ref "SENSOR1") (pin "1") (pinfunction "INT_1") (pintype "unspecified+no_connect"))
    )
    (net (code "27") (name "unconnected-(SENSOR1-INT{slash}TRIG-Pad7)") (class "Default")
      (node (ref "SENSOR1") (pin "7") (pinfunction "INT/TRIG_7") (pintype "unspecified+no_connect"))
    )
    (net (code "28") (name "unconnected-(SENSOR1-MISO-Pad6)") (class "Default")
      (node (ref "SENSOR1") (pin "6") (pinfunction "MISO_6") (pintype "unspecified+no_connect"))
    )
    (net (code "29") (name "unconnected-(SENSOR1-N{slash}C-Pad4)") (class "Default")
      (node (ref "SENSOR1") (pin "4") (pinfunction "N/C_4") (pintype "unspecified+no_connect"))
    )
    (net (code "30") (name "unconnected-(SENSOR1-N{slash}C-Pad9)") (class "Default")
      (node (ref "SENSOR1") (pin "9") (pinfunction "N/C_9") (pintype "unspecified+no_connect"))
    )
    (net (code "31") (name "unconnected-(SENSOR1-N{slash}C-Pad10)") (class "Default")
      (node (ref "SENSOR1") (pin "10") (pinfunction "N/C_10") (pintype "unspecified+no_connect"))
    )
    (net (code "32") (name "unconnected-(SENSOR1-N{slash}C-Pad14)") (class "Default")
      (node (ref "SENSOR1") (pin "14") (pinfunction "N/C_14") (pintype "unspecified+no_connect"))
    )
    (net (code "33") (name "unconnected-(SENSOR1-N{slash}C-Pad16)") (class "Default")
      (node (ref "SENSOR1") (pin "16") (pinfunction "N/C_16") (pintype "unspecified+no_connect"))
    )
    (net (code "34") (name "unconnected-(SENSOR2-INT-Pad1)") (class "Default")
      (node (ref "SENSOR2") (pin "1") (pinfunction "INT_1") (pintype "unspecified+no_connect"))
    )
    (net (code "35") (name "unconnected-(SENSOR2-INT{slash}TRIG-Pad7)") (class "Default")
      (node (ref "SENSOR2") (pin "7") (pinfunction "INT/TRIG_7") (pintype "unspecified+no_connect"))
    )
    (net (code "36") (name "unconnected-(SENSOR2-MISO-Pad6)") (class "Default")
      (node (ref "SENSOR2") (pin "6") (pinfunction "MISO_6") (pintype "unspecified+no_connect"))
    )
    (net (code "37") (name "unconnected-(SENSOR2-N{slash}C-Pad4)") (class "Default")
      (node (ref "SENSOR2") (pin "4") (pinfunction "N/C_4") (pintype "unspecified+no_connect"))
    )
    (net (code "38") (name "unconnected-(SENSOR2-N{slash}C-Pad9)") (class "Default")
      (node (ref "SENSOR2") (pin "9") (pinfunction "N/C_9") (pintype "unspecified+no_connect"))
    )
    (net (code "39") (name "unconnected-(SENSOR2-N{slash}C-Pad10)") (class "Default")
      (node (ref "SENSOR2") (pin "10") (pinfunction "N/C_10") (pintype "unspecified+no_connect"))
    )
    (net (code "40") (name "unconnected-(SENSOR2-N{slash}C-Pad14)") (class "Default")
      (node (ref "SENSOR2") (pin "14") (pinfunction "N/C_14") (pintype "unspecified+no_connect"))
    )
    (net (code "41") (name "unconnected-(SENSOR2-N{slash}C-Pad16)") (class "Default")
      (node (ref "SENSOR2") (pin "16") (pinfunction "N/C_16") (pintype "unspecified+no_connect"))
    )
    (net (code "42") (name "unconnected-(SENSOR3-INT-Pad1)") (class "Default")
      (node (ref "SENSOR3") (pin "1") (pinfunction "INT_1") (pintype "unspecified+no_connect"))
    )
    (net (code "43") (name "unconnected-(SENSOR3-INT{slash}TRIG-Pad7)") (class "Default")
      (node (ref "SENSOR3") (pin "7") (pinfunction "INT/TRIG_7") (pintype "unspecified+no_connect"))
    )
    (net (code "44") (name "unconnected-(SENSOR3-MISO-Pad6)") (class "Default")
      (node (ref "SENSOR3") (pin "6") (pinfunction "MISO_6") (pintype "unspecified+no_connect"))
    )
    (net (code "45") (name "unconnected-(SENSOR3-N{slash}C-Pad4)") (class "Default")
      (node (ref "SENSOR3") (pin "4") (pinfunction "N/C_4") (pintype "unspecified+no_connect"))
    )
    (net (code "46") (name "unconnected-(SENSOR3-N{slash}C-Pad9)") (class "Default")
      (node (ref "SENSOR3") (pin "9") (pinfunction "N/C_9") (pintype "unspecified+no_connect"))
    )
    (net (code "47") (name "unconnected-(SENSOR3-N{slash}C-Pad10)") (class "Default")
      (node (ref "SENSOR3") (pin "10") (pinfunction "N/C_10") (pintype "unspecified+no_connect"))
    )
    (net (code "48") (name "unconnected-(SENSOR3-N{slash}C-Pad14)") (class "Default")
      (node (ref "SENSOR3") (pin "14") (pinfunction "N/C_14") (pintype "unspecified+no_connect"))
    )
    (net (code "49") (name "unconnected-(SENSOR3-N{slash}C-Pad16)") (class "Default")
      (node (ref "SENSOR3") (pin "16") (pinfunction "N/C_16") (pintype "unspecified+no_connect"))
    )
    (net (code "50") (name "unconnected-(SENSOR4-INT-Pad1)") (class "Default")
      (node (ref "SENSOR4") (pin "1") (pinfunction "INT_1") (pintype "unspecified+no_connect"))
    )
    (net (code "51") (name "unconnected-(SENSOR4-INT{slash}TRIG-Pad7)") (class "Default")
      (node (ref "SENSOR4") (pin "7") (pinfunction "INT/TRIG_7") (pintype "unspecified+no_connect"))
    )
    (net (code "52") (name "unconnected-(SENSOR4-MISO-Pad6)") (class "Default")
      (node (ref "SENSOR4") (pin "6") (pinfunction "MISO_6") (pintype "unspecified+no_connect"))
    )
    (net (code "53") (name "unconnected-(SENSOR4-N{slash}C-Pad4)") (class "Default")
      (node (ref "SENSOR4") (pin "4") (pinfunction "N/C_4") (pintype "unspecified+no_connect"))
    )
    (net (code "54") (name "unconnected-(SENSOR4-N{slash}C-Pad9)") (class "Default")
      (node (ref "SENSOR4") (pin "9") (pinfunction "N/C_9") (pintype "unspecified+no_connect"))
    )
    (net (code "55") (name "unconnected-(SENSOR4-N{slash}C-Pad10)") (class "Default")
      (node (ref "SENSOR4") (pin "10") (pinfunction "N/C_10") (pintype "unspecified+no_connect"))
    )
    (net (code "56") (name "unconnected-(SENSOR4-N{slash}C-Pad14)") (class "Default")
      (node (ref "SENSOR4") (pin "14") (pinfunction "N/C_14") (pintype "unspecified+no_connect"))
    )
    (net (code "57") (name "unconnected-(SENSOR4-N{slash}C-Pad16)") (class "Default")
      (node (ref "SENSOR4") (pin "16") (pinfunction "N/C_16") (pintype "unspecified+no_connect"))
    )
    (net (code "58") (name "unconnected-(U1-GPIO0-Pad2)") (class "Default")
      (node (ref "U1") (pin "2") (pinfunction "GPIO0_2") (pintype "unspecified"))
    )
    (net (code "59") (name "unconnected-(U1-GPIO1-Pad3)") (class "Default")
      (node (ref "U1") (pin "3") (pinfunction "GPIO1_3") (pintype "unspecified"))
    )
    (net (code "60") (name "unconnected-(U1-GPIO2-Pad4)") (class "Default")
      (node (ref "U1") (pin "4") (pinfunction "GPIO2_4") (pintype "unspecified"))
    )
    (net (code "61") (name "unconnected-(U1-GPIO3-Pad5)") (class "Default")
      (node (ref "U1") (pin "5") (pinfunction "GPIO3_5") (pintype "unspecified"))
    )
    (net (code "62") (name "unconnected-(U1-GPIO4-Pad7)") (class "Default")
      (node (ref "U1") (pin "7") (pinfunction "GPIO4_7") (pintype "unspecified"))
    )
    (net (code "63") (name "unconnected-(U1-GPIO5-Pad8)") (class "Default")
      (node (ref "U1") (pin "8") (pinfunction "GPIO5_8") (pintype "unspecified"))
    )
    (net (code "64") (name "unconnected-(U1-GPIO6-Pad9)") (class "Default")
      (node (ref "U1") (pin "9") (pinfunction "GPIO6_9") (pintype "unspecified"))
    )
    (net (code "65") (name "unconnected-(U1-GPIO7-Pad10)") (class "Default")
      (node (ref "U1") (pin "10") (pinfunction "GPIO7_10") (pintype "unspecified"))
    )
    (net (code "66") (name "unconnected-(U1-GPIO8-Pad12)") (class "Default")
      (node (ref "U1") (pin "12") (pinfunction "GPIO8_12") (pintype "unspecified"))
    )
    (net (code "67") (name "unconnected-(U1-GPIO9-Pad13)") (class "Default")
      (node (ref "U1") (pin "13") (pinfunction "GPIO9_13") (pintype "unspecified"))
    )
    (net (code "68") (name "unconnected-(U1-GPIO10-Pad14)") (class "Default")
      (node (ref "U1") (pin "14") (pinfunction "GPIO10_14") (pintype "unspecified"))
    )
    (net (code "69") (name "unconnected-(U1-GPIO11-Pad15)") (class "Default")
      (node (ref "U1") (pin "15") (pinfunction "GPIO11_15") (pintype "unspecified"))
    )
    (net (code "70") (name "unconnected-(U1-GPIO12-Pad16)") (class "Default")
      (node (ref "U1") (pin "16") (pinfunction "GPIO12_16") (pintype "unspecified"))
    )
    (net (code "71") (name "unconnected-(U1-GPIO13-Pad17)") (class "Default")
      (node (ref "U1") (pin "17") (pinfunction "GPIO13_17") (pintype "unspecified"))
    )
    (net (code "72") (name "unconnected-(U1-GPIO14-Pad18)") (class "Default")
      (node (ref "U1") (pin "18") (pinfunction "GPIO14_18") (pintype "unspecified"))
    )
    (net (code "73") (name "unconnected-(U1-GPIO15-Pad19)") (class "Default")
      (node (ref "U1") (pin "19") (pinfunction "GPIO15_19") (pintype "unspecified"))
    )
    (net (code "74") (name "unconnected-(U1-GPIO18-Pad29)") (class "Default")
      (node (ref "U1") (pin "29") (pinfunction "GPIO18_29") (pintype "unspecified"))
    )
    (net (code "75") (name "unconnected-(U1-GPIO19-Pad31)") (class "Default")
      (node (ref "U1") (pin "31") (pinfunction "GPIO19_31") (pintype "unspecified"))
    )
    (net (code "76") (name "unconnected-(U1-GPIO20-Pad32)") (class "Default")
      (node (ref "U1") (pin "32") (pinfunction "GPIO20_32") (pintype "unspecified"))
    )
    (net (code "77") (name "unconnected-(U1-GPIO21-Pad33)") (class "Default")
      (node (ref "U1") (pin "33") (pinfunction "GPIO21_33") (pintype "unspecified"))
    )
    (net (code "78") (name "unconnected-(U1-GPIO22-Pad34)") (class "Default")
      (node (ref "U1") (pin "34") (pinfunction "GPIO22_34") (pintype "unspecified"))
    )
    (net (code "79") (name "unconnected-(U1-GPIO23-Pad35)") (class "Default")
      (node (ref "U1") (pin "35") (pinfunction "GPIO23_35") (pintype "unspecified"))
    )
    (net (code "80") (name "unconnected-(U1-GPIO24-Pad36)") (class "Default")
      (node (ref "U1") (pin "36") (pinfunction "GPIO24_36") (pintype "unspecified"))
    )
    (net (code "81") (name "unconnected-(U1-GPIO25-Pad37)") (class "Default")
      (node (ref "U1") (pin "37") (pinfunction "GPIO25_37") (pintype "unspecified"))
    )
    (net (code "82") (name "unconnected-(U1-GPIO27_ADC1-Pad41)") (class "Default")
      (node (ref "U1") (pin "41") (pinfunction "GPIO27_ADC1_41") (pintype "unspecified"))
    )
    (net (code "83") (name "unconnected-(U1-GPIO28_ADC2-Pad42)") (class "Default")
      (node (ref "U1") (pin "42") (pinfunction "GPIO28_ADC2_42") (pintype "unspecified"))
    )
    (net (code "84") (name "unconnected-(U1-GPIO29_ADC3-Pad43)") (class "Default")
      (node (ref "U1") (pin "43") (pinfunction "GPIO29_ADC3_43") (pintype "unspecified"))
    )
    (net (code "85") (name "unconnected-(U1-SWCLK-Pad24)") (class "Default")
      (node (ref "U1") (pin "24") (pinfunction "SWCLK_24") (pintype "unspecified"))
    )
    (net (code "86") (name "unconnected-(U1-SWDIO-Pad25)") (class "Default")
      (node (ref "U1") (pin "25") (pinfunction "SWDIO_25") (pintype "unspecified"))
    )
  )
)
